# FPGA_Configuration.net
KiCad netlist of a schematic drawn in Altium Designer
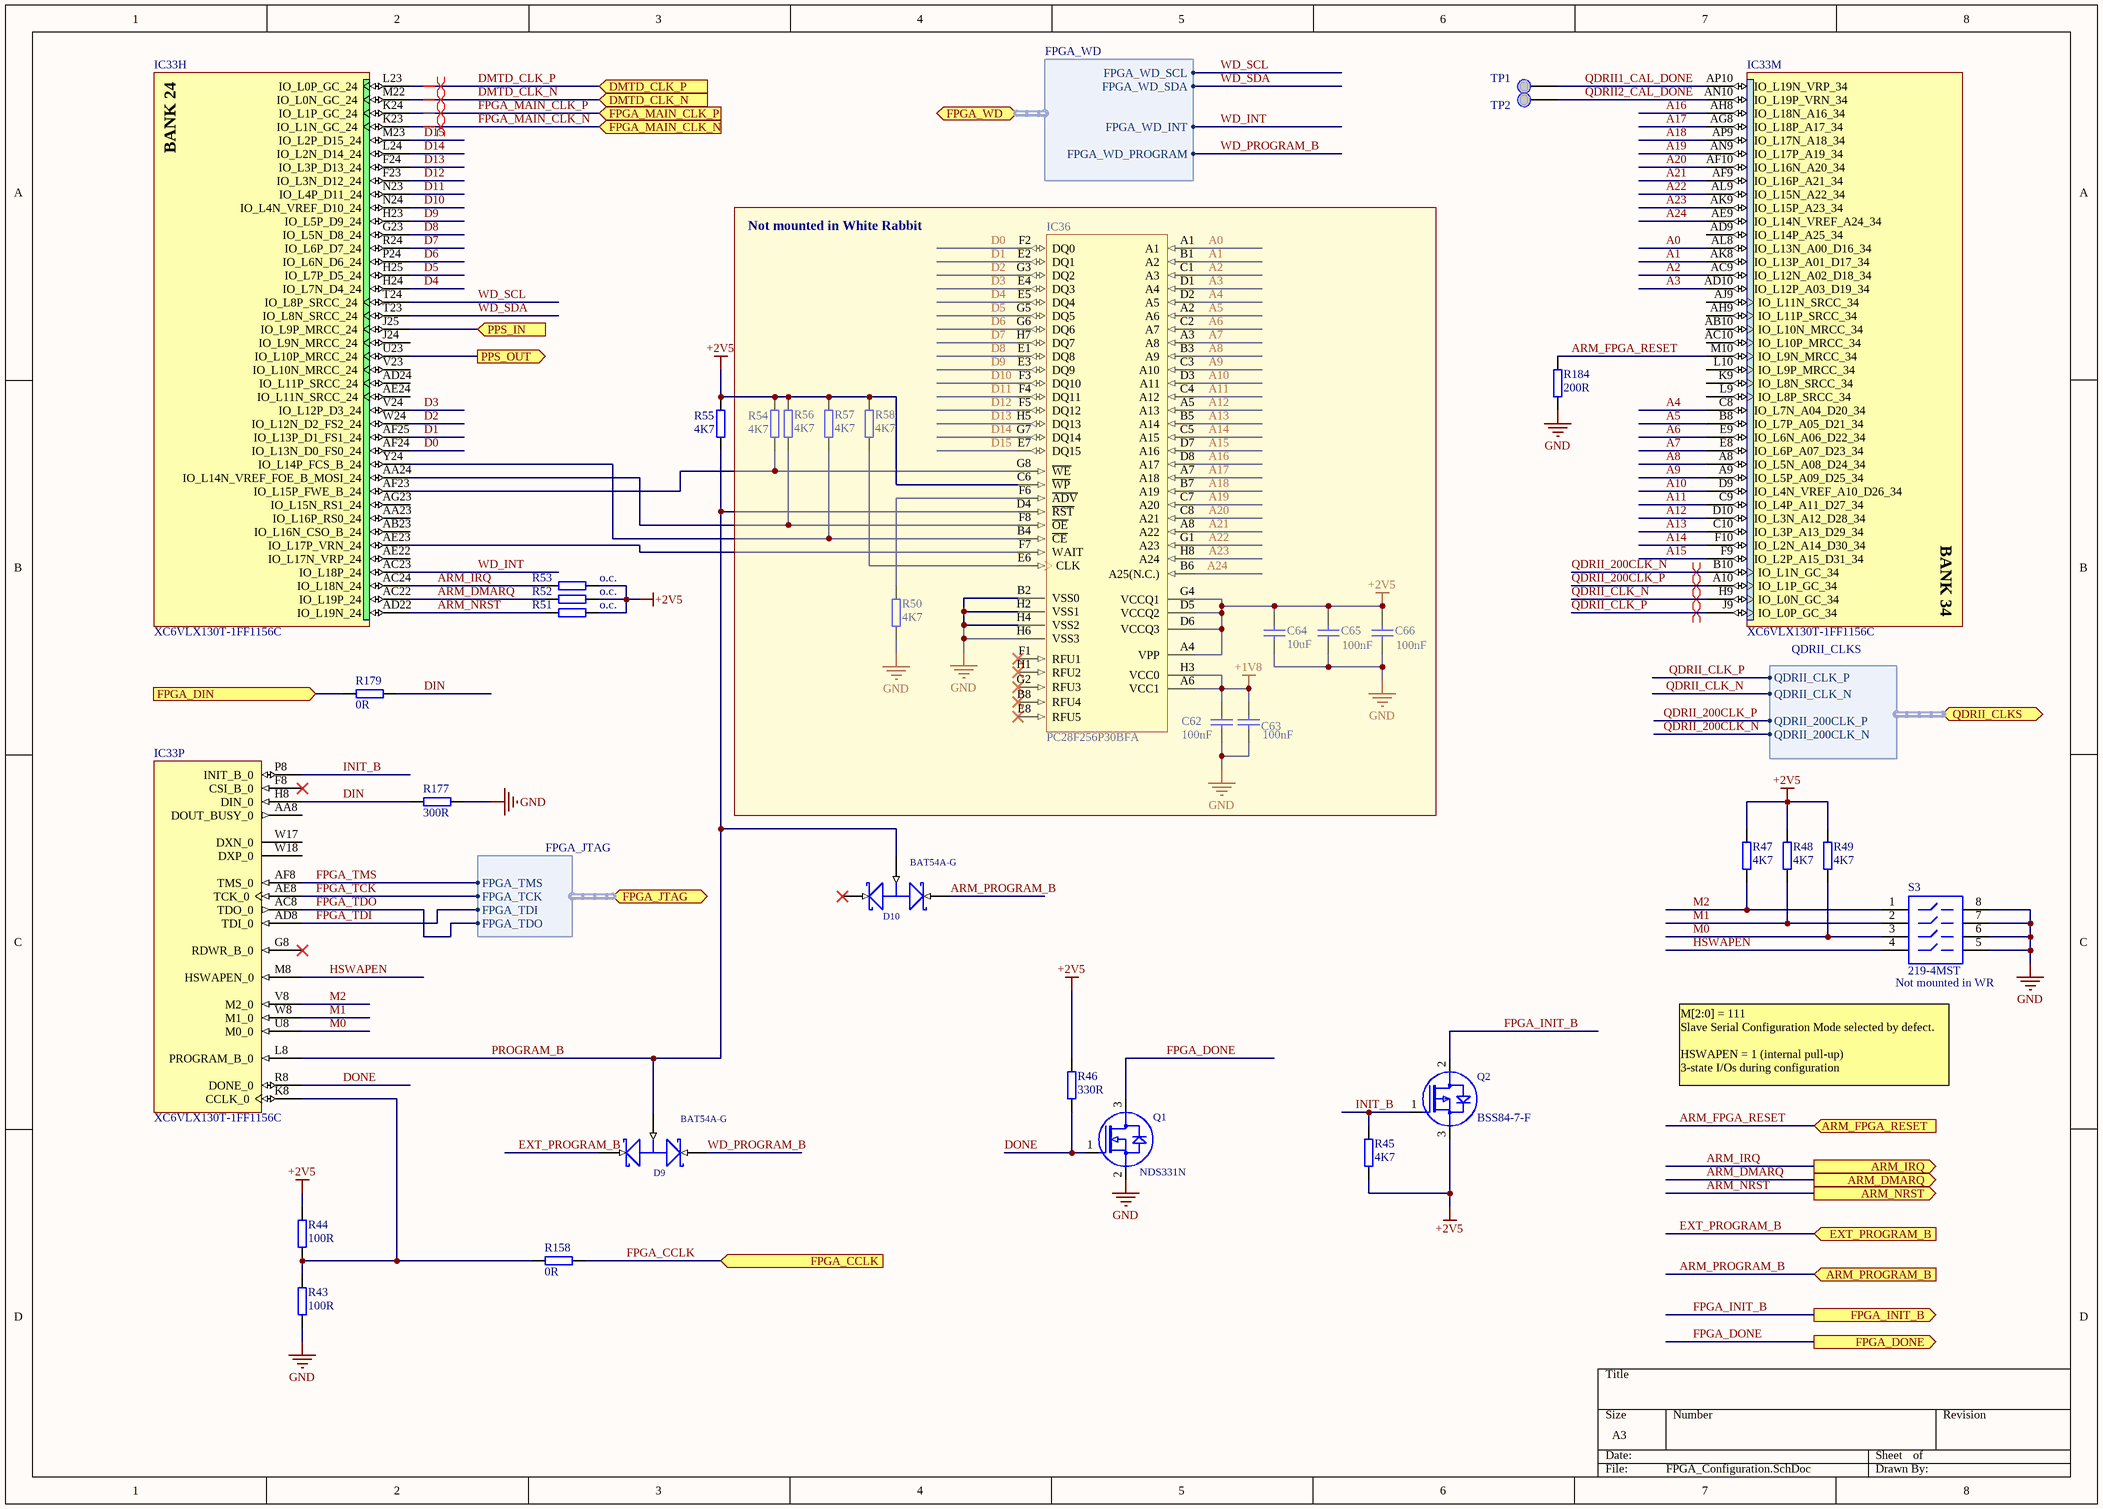
[diagram p0: FPGA_Configuration.SchDoc]

(export (version "E")
  (design (tool "Eeschema 10.0.6"))
  (components
    (comp (ref "C62")
      (value "100nF")
      (footprint "CC1005-0402")
      (description "Capacitor")
      (fields
        (field (name "TOLERANCE") "±10%")
        (field (name "VOLTAGE") "16V")
        (field (name "PUBLISHER") "Altium Limited")
      )
      (libsource (lib "wr_switch") (part "Cap"))
    )
    (comp (ref "C63")
      (value "100nF")
      (footprint "CC1005-0402")
      (description "Capacitor")
      (fields
        (field (name "TOLERANCE") "±10%")
        (field (name "VOLTAGE") "16V")
        (field (name "PUBLISHER") "Altium Limited")
      )
      (libsource (lib "wr_switch") (part "Cap"))
    )
    (comp (ref "C64")
      (value "10uF")
      (footprint "CC1608-0603")
      (description "Capacitor")
      (fields
        (field (name "TOLERANCE") "±20%")
        (field (name "VOLTAGE") "6.3V")
        (field (name "PUBLISHER") "Altium Limited")
      )
      (libsource (lib "wr_switch") (part "Cap"))
    )
    (comp (ref "C65")
      (value "100nF")
      (footprint "CC1005-0402")
      (description "Capacitor")
      (fields
        (field (name "TOLERANCE") "±10%")
        (field (name "VOLTAGE") "16V")
        (field (name "PUBLISHER") "Altium Limited")
      )
      (libsource (lib "wr_switch") (part "Cap"))
    )
    (comp (ref "C66")
      (value "100nF")
      (footprint "CC1005-0402")
      (description "Capacitor")
      (fields
        (field (name "TOLERANCE") "±10%")
        (field (name "VOLTAGE") "16V")
        (field (name "PUBLISHER") "Altium Limited")
      )
      (libsource (lib "wr_switch") (part "Cap"))
    )
    (comp (ref "D9")
      (value "BAT54A-G")
      (footprint "SOT23")
      (description "Schottky Barrier Double Diode")
      (fields (field (name "PUBLISHER") "Altium Limited"))
      (libsource (lib "wr_switch") (part "BAT54A.1"))
    )
    (comp (ref "D10")
      (value "BAT54A-G")
      (footprint "SOT23")
      (description "Schottky Barrier Double Diode")
      (fields (field (name "PUBLISHER") "Altium Limited"))
      (libsource (lib "wr_switch") (part "BAT54A.1"))
    )
    (comp (ref "IC33")
      (value "XC6VLX130T-1FF1156C")
      (footprint "FF1156")
      (fields (field (name "PUBLISHER") "Altium Limited"))
      (libsource (lib "Xilinx Virtex-6") (part "XC6VLX130T-1FF1156C"))
    )
    (comp (ref "IC36")
      (value "PC28F256P30BFA")
      (footprint "BGA64C100P8X8_1300X1000X120")
      (description "NOR Flash Memory, 256Mbit")
      (libsource (lib "wr_switch") (part "PC28F256P30BFA"))
    )
    (comp (ref "Q1")
      (value "NDS331N")
      (footprint "SOT23-3")
      (description "N-Channel Logic Level Enhancement Mode Field Effect Transistor")
      (libsource (lib "wr_switch") (part "NDS331N"))
    )
    (comp (ref "Q2")
      (value "FET-3PIN")
      (footprint "SOT-23")
      (description "P-Channel Logic Level Enhancement Mode Field Effect Transistor")
      (fields (field (name "MANF") "Diodes Inc.") (field (name "MANF_P/N") "BSS84-7-F"))
      (libsource (lib "wr_switch") (part "BSS84-7-F"))
    )
    (comp (ref "R43")
      (value "100R")
      (footprint "0402")
      (description "SMD Resistor")
      (fields (field (name "TOLERANCE") "±1%"))
      (libsource (lib "wr_switch") (part "RES_SMD"))
    )
    (comp (ref "R44")
      (value "100R")
      (footprint "0402")
      (description "SMD Resistor")
      (fields (field (name "TOLERANCE") "±1%"))
      (libsource (lib "wr_switch") (part "RES_SMD"))
    )
    (comp (ref "R45")
      (value "4K7")
      (footprint "0402")
      (description "SMD Resistor")
      (fields (field (name "TOLERANCE") "±1%"))
      (libsource (lib "wr_switch") (part "RES_SMD"))
    )
    (comp (ref "R46")
      (value "330R")
      (footprint "0402")
      (description "SMD Resistor")
      (fields (field (name "TOLERANCE") "±1%"))
      (libsource (lib "wr_switch") (part "RES_SMD"))
    )
    (comp (ref "R47")
      (value "4K7")
      (footprint "0402")
      (description "SMD Resistor")
      (fields (field (name "TOLERANCE") "±1%"))
      (libsource (lib "wr_switch") (part "RES_SMD"))
    )
    (comp (ref "R48")
      (value "4K7")
      (footprint "0402")
      (description "SMD Resistor")
      (fields (field (name "TOLERANCE") "±1%"))
      (libsource (lib "wr_switch") (part "RES_SMD"))
    )
    (comp (ref "R49")
      (value "4K7")
      (footprint "0402")
      (description "SMD Resistor")
      (fields (field (name "TOLERANCE") "±1%"))
      (libsource (lib "wr_switch") (part "RES_SMD"))
    )
    (comp (ref "R50")
      (value "4K7")
      (footprint "0402")
      (description "SMD Resistor")
      (fields (field (name "TOLERANCE") "±1%"))
      (libsource (lib "wr_switch") (part "RES_SMD"))
    )
    (comp (ref "R51")
      (value "o.c.")
      (footprint "0402")
      (description "SMD Resistor")
      (libsource (lib "wr_switch") (part "RES_SMD"))
    )
    (comp (ref "R52")
      (value "o.c.")
      (footprint "0402")
      (description "SMD Resistor")
      (libsource (lib "wr_switch") (part "RES_SMD"))
    )
    (comp (ref "R53")
      (value "o.c.")
      (footprint "0402")
      (description "SMD Resistor")
      (libsource (lib "wr_switch") (part "RES_SMD"))
    )
    (comp (ref "R54")
      (value "4K7")
      (footprint "0402")
      (description "SMD Resistor")
      (fields (field (name "TOLERANCE") "±1%"))
      (libsource (lib "wr_switch") (part "RES_SMD"))
    )
    (comp (ref "R55")
      (value "4K7")
      (footprint "0402")
      (description "SMD Resistor")
      (fields (field (name "TOLERANCE") "±1%"))
      (libsource (lib "wr_switch") (part "RES_SMD"))
    )
    (comp (ref "R56")
      (value "4K7")
      (footprint "0402")
      (description "SMD Resistor")
      (fields (field (name "TOLERANCE") "±1%"))
      (libsource (lib "wr_switch") (part "RES_SMD"))
    )
    (comp (ref "R57")
      (value "4K7")
      (footprint "0402")
      (description "SMD Resistor")
      (fields (field (name "TOLERANCE") "±1%"))
      (libsource (lib "wr_switch") (part "RES_SMD"))
    )
    (comp (ref "R58")
      (value "4K7")
      (footprint "0402")
      (description "SMD Resistor")
      (fields (field (name "TOLERANCE") "±1%"))
      (libsource (lib "wr_switch") (part "RES_SMD"))
    )
    (comp (ref "R158")
      (value "0R")
      (footprint "0402")
      (description "SMD Resistor")
      (fields (field (name "TOLERANCE") "Jumper"))
      (libsource (lib "wr_switch") (part "RES_SMD"))
    )
    (comp (ref "R177")
      (value "300R")
      (footprint "0402")
      (description "SMD Resistor")
      (fields (field (name "TOLERANCE") "±1%"))
      (libsource (lib "wr_switch") (part "RES_SMD"))
    )
    (comp (ref "R179")
      (value "0R")
      (footprint "0402")
      (description "SMD Resistor")
      (fields (field (name "TOLERANCE") "Jumper"))
      (libsource (lib "wr_switch") (part "RES_SMD"))
    )
    (comp (ref "R184")
      (value "200R")
      (footprint "0402")
      (description "SMD Resistor")
      (fields (field (name "TOLERANCE") "±1%"))
      (libsource (lib "wr_switch") (part "RES_SMD"))
    )
    (comp (ref "S3")
      (value "219-4MST")
      (footprint "7S_WR:NHDS-8")
      (description "4 Positions DIP SWITCH")
      (fields
        (field (name "MANUFACTURER") "CTS Electrocomponents")
        (field (name "MOUNTED") "Not mounted in WR")
      )
      (libsource (lib "wr_switch") (part "SW-DIP4"))
    )
    (comp (ref "TP1")
      (value "Test Point")
      (footprint "TEST_PAD_1mm")
      (description "SMD 1mm Test Point")
      (libsource (lib "wr_switch") (part "TEST_POINT"))
    )
    (comp (ref "TP2")
      (value "Test Point")
      (footprint "TEST_PAD_1mm")
      (description "SMD 1mm Test Point")
      (libsource (lib "wr_switch") (part "TEST_POINT"))
    )
  )
  (nets
    (net (code "4") (name "+1V8") (class "Default")
      (node (ref "C62") (pin "2") (pinfunction "2_2") (pintype "passive"))
      (node (ref "C63") (pin "2") (pinfunction "2_2") (pintype "passive"))
      (node (ref "IC36") (pin "A6") (pinfunction "VCC1_A6") (pintype "power_in"))
      (node (ref "IC36") (pin "H3") (pinfunction "VCC0_H3") (pintype "power_in"))
    )
    (net (code "5") (name "+2V5") (class "Default")
      (node (ref "C64") (pin "2") (pinfunction "2_2") (pintype "passive"))
      (node (ref "C65") (pin "2") (pinfunction "2_2") (pintype "passive"))
      (node (ref "C66") (pin "2") (pinfunction "2_2") (pintype "passive"))
      (node (ref "IC36") (pin "A4") (pinfunction "VPP_A4") (pintype "passive"))
      (node (ref "IC36") (pin "C6") (pinfunction "~{WP}_C6") (pintype "input"))
      (node (ref "IC36") (pin "D5") (pinfunction "VCCQ2_D5") (pintype "power_in"))
      (node (ref "IC36") (pin "D6") (pinfunction "VCCQ3_D6") (pintype "power_in"))
      (node (ref "IC36") (pin "G4") (pinfunction "VCCQ1_G4") (pintype "power_in"))
      (node (ref "Q2") (pin "3") (pinfunction "SOURCE_3") (pintype "passive"))
      (node (ref "R44") (pin "2") (pinfunction "2_2") (pintype "passive"))
      (node (ref "R45") (pin "1") (pinfunction "1_1") (pintype "passive"))
      (node (ref "R46") (pin "2") (pinfunction "2_2") (pintype "passive"))
      (node (ref "R47") (pin "2") (pinfunction "2_2") (pintype "passive"))
      (node (ref "R48") (pin "2") (pinfunction "2_2") (pintype "passive"))
      (node (ref "R49") (pin "2") (pinfunction "2_2") (pintype "passive"))
      (node (ref "R51") (pin "1") (pinfunction "1_1") (pintype "passive"))
      (node (ref "R52") (pin "1") (pinfunction "1_1") (pintype "passive"))
      (node (ref "R53") (pin "1") (pinfunction "1_1") (pintype "passive"))
      (node (ref "R54") (pin "2") (pinfunction "2_2") (pintype "passive"))
      (node (ref "R55") (pin "2") (pinfunction "2_2") (pintype "passive"))
      (node (ref "R56") (pin "2") (pinfunction "2_2") (pintype "passive"))
      (node (ref "R57") (pin "2") (pinfunction "2_2") (pintype "passive"))
      (node (ref "R58") (pin "2") (pinfunction "2_2") (pintype "passive"))
    )
    (net (code "6") (name "/A0") (class "Default")
      (node (ref "IC33") (pin "AL8") (pinfunction "IO_L13N_A00_D16_34_AL8") (pintype "bidirectional"))
      (node (ref "IC36") (pin "A1") (pinfunction "A1_A1") (pintype "input"))
    )
    (net (code "7") (name "/A1") (class "Default")
      (node (ref "IC33") (pin "AK8") (pinfunction "IO_L13P_A01_D17_34_AK8") (pintype "bidirectional"))
      (node (ref "IC36") (pin "B1") (pinfunction "A2_B1") (pintype "input"))
    )
    (net (code "8") (name "/A2") (class "Default")
      (node (ref "IC33") (pin "AC9") (pinfunction "IO_L12N_A02_D18_34_AC9") (pintype "bidirectional"))
      (node (ref "IC36") (pin "C1") (pinfunction "A3_C1") (pintype "input"))
    )
    (net (code "9") (name "/A3") (class "Default")
      (node (ref "IC33") (pin "AD10") (pinfunction "IO_L12P_A03_D19_34_AD10") (pintype "bidirectional"))
      (node (ref "IC36") (pin "D1") (pinfunction "A4_D1") (pintype "input"))
    )
    (net (code "10") (name "/A4") (class "Default")
      (node (ref "IC33") (pin "C8") (pinfunction "IO_L7N_A04_D20_34_C8") (pintype "bidirectional"))
      (node (ref "IC36") (pin "D2") (pinfunction "A5_D2") (pintype "input"))
    )
    (net (code "11") (name "/A5") (class "Default")
      (node (ref "IC33") (pin "B8") (pinfunction "IO_L7P_A05_D21_34_B8") (pintype "bidirectional"))
      (node (ref "IC36") (pin "A2") (pinfunction "A6_A2") (pintype "input"))
    )
    (net (code "12") (name "/A6") (class "Default")
      (node (ref "IC33") (pin "E9") (pinfunction "IO_L6N_A06_D22_34_E9") (pintype "bidirectional"))
      (node (ref "IC36") (pin "C2") (pinfunction "A7_C2") (pintype "input"))
    )
    (net (code "13") (name "/A7") (class "Default")
      (node (ref "IC33") (pin "E8") (pinfunction "IO_L6P_A07_D23_34_E8") (pintype "bidirectional"))
      (node (ref "IC36") (pin "A3") (pinfunction "A8_A3") (pintype "input"))
    )
    (net (code "14") (name "/A8") (class "Default")
      (node (ref "IC33") (pin "A8") (pinfunction "IO_L5N_A08_D24_34_A8") (pintype "bidirectional"))
      (node (ref "IC36") (pin "B3") (pinfunction "A9_B3") (pintype "input"))
    )
    (net (code "15") (name "/A9") (class "Default")
      (node (ref "IC33") (pin "A9") (pinfunction "IO_L5P_A09_D25_34_A9") (pintype "bidirectional"))
      (node (ref "IC36") (pin "C3") (pinfunction "A10_C3") (pintype "input"))
    )
    (net (code "16") (name "/A10") (class "Default")
      (node (ref "IC33") (pin "D9") (pinfunction "IO_L4N_VREF_A10_D26_34_D9") (pintype "bidirectional"))
      (node (ref "IC36") (pin "D3") (pinfunction "A11_D3") (pintype "input"))
    )
    (net (code "17") (name "/A11") (class "Default")
      (node (ref "IC33") (pin "C9") (pinfunction "IO_L4P_A11_D27_34_C9") (pintype "bidirectional"))
      (node (ref "IC36") (pin "C4") (pinfunction "A12_C4") (pintype "input"))
    )
    (net (code "18") (name "/A12") (class "Default")
      (node (ref "IC33") (pin "D10") (pinfunction "IO_L3N_A12_D28_34_D10") (pintype "bidirectional"))
      (node (ref "IC36") (pin "A5") (pinfunction "A13_A5") (pintype "input"))
    )
    (net (code "19") (name "/A13") (class "Default")
      (node (ref "IC33") (pin "C10") (pinfunction "IO_L3P_A13_D29_34_C10") (pintype "bidirectional"))
      (node (ref "IC36") (pin "B5") (pinfunction "A14_B5") (pintype "input"))
    )
    (net (code "20") (name "/A14") (class "Default")
      (node (ref "IC33") (pin "F10") (pinfunction "IO_L2N_A14_D30_34_F10") (pintype "bidirectional"))
      (node (ref "IC36") (pin "C5") (pinfunction "A15_C5") (pintype "input"))
    )
    (net (code "21") (name "/A15") (class "Default")
      (node (ref "IC33") (pin "F9") (pinfunction "IO_L2P_A15_D31_34_F9") (pintype "bidirectional"))
      (node (ref "IC36") (pin "D7") (pinfunction "A16_D7") (pintype "input"))
    )
    (net (code "22") (name "/A16") (class "Default")
      (node (ref "IC33") (pin "AH8") (pinfunction "IO_L18N_A16_34_AH8") (pintype "bidirectional"))
      (node (ref "IC36") (pin "D8") (pinfunction "A17_D8") (pintype "input"))
    )
    (net (code "23") (name "/A17") (class "Default")
      (node (ref "IC33") (pin "AG8") (pinfunction "IO_L18P_A17_34_AG8") (pintype "bidirectional"))
      (node (ref "IC36") (pin "A7") (pinfunction "A18_A7") (pintype "input"))
    )
    (net (code "24") (name "/A18") (class "Default")
      (node (ref "IC33") (pin "AP9") (pinfunction "IO_L17N_A18_34_AP9") (pintype "bidirectional"))
      (node (ref "IC36") (pin "B7") (pinfunction "A19_B7") (pintype "input"))
    )
    (net (code "25") (name "/A19") (class "Default")
      (node (ref "IC33") (pin "AN9") (pinfunction "IO_L17P_A19_34_AN9") (pintype "bidirectional"))
      (node (ref "IC36") (pin "C7") (pinfunction "A20_C7") (pintype "input"))
    )
    (net (code "26") (name "/A20") (class "Default")
      (node (ref "IC33") (pin "AF10") (pinfunction "IO_L16N_A20_34_AF10") (pintype "bidirectional"))
      (node (ref "IC36") (pin "C8") (pinfunction "A21_C8") (pintype "input"))
    )
    (net (code "27") (name "/A21") (class "Default")
      (node (ref "IC33") (pin "AF9") (pinfunction "IO_L16P_A21_34_AF9") (pintype "bidirectional"))
      (node (ref "IC36") (pin "A8") (pinfunction "A22_A8") (pintype "input"))
    )
    (net (code "28") (name "/A22") (class "Default")
      (node (ref "IC33") (pin "AL9") (pinfunction "IO_L15N_A22_34_AL9") (pintype "bidirectional"))
      (node (ref "IC36") (pin "G1") (pinfunction "A23_G1") (pintype "input"))
    )
    (net (code "29") (name "/A23") (class "Default")
      (node (ref "IC33") (pin "AK9") (pinfunction "IO_L15P_A23_34_AK9") (pintype "bidirectional"))
      (node (ref "IC36") (pin "H8") (pinfunction "A24_H8") (pintype "input"))
    )
    (net (code "30") (name "/A24") (class "Default")
      (node (ref "IC33") (pin "AE9") (pinfunction "IO_L14N_VREF_A24_34_AE9") (pintype "bidirectional"))
      (node (ref "IC36") (pin "B6") (pinfunction "A25(N.C.)_B6") (pintype "input"))
    )
    (net (code "31") (name "/ARM_DMARQ") (class "Default")
      (node (ref "IC33") (pin "AC22") (pinfunction "IO_L19P_24_AC22") (pintype "bidirectional"))
      (node (ref "R52") (pin "2") (pinfunction "2_2") (pintype "passive"))
    )
    (net (code "32") (name "/ARM_FPGA_RESET") (class "Default")
      (node (ref "IC33") (pin "M10") (pinfunction "IO_L9N_MRCC_34_M10") (pintype "bidirectional"))
      (node (ref "R184") (pin "2") (pinfunction "2_2") (pintype "passive"))
    )
    (net (code "33") (name "/ARM_IRQ") (class "Default")
      (node (ref "IC33") (pin "AC24") (pinfunction "IO_L18N_24_AC24") (pintype "bidirectional"))
      (node (ref "R53") (pin "2") (pinfunction "2_2") (pintype "passive"))
    )
    (net (code "34") (name "/ARM_NRST") (class "Default")
      (node (ref "IC33") (pin "AD22") (pinfunction "IO_L19N_24_AD22") (pintype "bidirectional"))
      (node (ref "R51") (pin "2") (pinfunction "2_2") (pintype "passive"))
    )
    (net (code "35") (name "/ARM_PROGRAM_B") (class "Default")
      (node (ref "D10") (pin "2") (pinfunction "K2_2") (pintype "input"))
    )
    (net (code "36") (name "/D0") (class "Default")
      (node (ref "IC33") (pin "AF24") (pinfunction "IO_L13N_D0_FS0_24_AF24") (pintype "bidirectional"))
      (node (ref "IC36") (pin "F2") (pinfunction "DQ0_F2") (pintype "bidirectional"))
    )
    (net (code "37") (name "/D1") (class "Default")
      (node (ref "IC33") (pin "AF25") (pinfunction "IO_L13P_D1_FS1_24_AF25") (pintype "bidirectional"))
      (node (ref "IC36") (pin "E2") (pinfunction "DQ1_E2") (pintype "bidirectional"))
    )
    (net (code "38") (name "/D2") (class "Default")
      (node (ref "IC33") (pin "W24") (pinfunction "IO_L12N_D2_FS2_24_W24") (pintype "bidirectional"))
      (node (ref "IC36") (pin "G3") (pinfunction "DQ2_G3") (pintype "bidirectional"))
    )
    (net (code "39") (name "/D3") (class "Default")
      (node (ref "IC33") (pin "V24") (pinfunction "IO_L12P_D3_24_V24") (pintype "bidirectional"))
      (node (ref "IC36") (pin "E4") (pinfunction "DQ3_E4") (pintype "bidirectional"))
    )
    (net (code "40") (name "/D4") (class "Default")
      (node (ref "IC33") (pin "H24") (pinfunction "IO_L7N_D4_24_H24") (pintype "bidirectional"))
      (node (ref "IC36") (pin "E5") (pinfunction "DQ4_E5") (pintype "bidirectional"))
    )
    (net (code "41") (name "/D5") (class "Default")
      (node (ref "IC33") (pin "H25") (pinfunction "IO_L7P_D5_24_H25") (pintype "bidirectional"))
      (node (ref "IC36") (pin "G5") (pinfunction "DQ5_G5") (pintype "bidirectional"))
    )
    (net (code "42") (name "/D6") (class "Default")
      (node (ref "IC33") (pin "P24") (pinfunction "IO_L6N_D6_24_P24") (pintype "bidirectional"))
      (node (ref "IC36") (pin "G6") (pinfunction "DQ6_G6") (pintype "bidirectional"))
    )
    (net (code "43") (name "/D7") (class "Default")
      (node (ref "IC33") (pin "R24") (pinfunction "IO_L6P_D7_24_R24") (pintype "bidirectional"))
      (node (ref "IC36") (pin "H7") (pinfunction "DQ7_H7") (pintype "bidirectional"))
    )
    (net (code "44") (name "/D8") (class "Default")
      (node (ref "IC33") (pin "G23") (pinfunction "IO_L5N_D8_24_G23") (pintype "bidirectional"))
      (node (ref "IC36") (pin "E1") (pinfunction "DQ8_E1") (pintype "bidirectional"))
    )
    (net (code "45") (name "/D9") (class "Default")
      (node (ref "IC33") (pin "H23") (pinfunction "IO_L5P_D9_24_H23") (pintype "bidirectional"))
      (node (ref "IC36") (pin "E3") (pinfunction "DQ9_E3") (pintype "bidirectional"))
    )
    (net (code "46") (name "/D10") (class "Default")
      (node (ref "IC33") (pin "N24") (pinfunction "IO_L4N_VREF_D10_24_N24") (pintype "bidirectional"))
      (node (ref "IC36") (pin "F3") (pinfunction "DQ10_F3") (pintype "bidirectional"))
    )
    (net (code "47") (name "/D11") (class "Default")
      (node (ref "IC33") (pin "N23") (pinfunction "IO_L4P_D11_24_N23") (pintype "bidirectional"))
      (node (ref "IC36") (pin "F4") (pinfunction "DQ11_F4") (pintype "bidirectional"))
    )
    (net (code "48") (name "/D12") (class "Default")
      (node (ref "IC33") (pin "F23") (pinfunction "IO_L3N_D12_24_F23") (pintype "bidirectional"))
      (node (ref "IC36") (pin "F5") (pinfunction "DQ12_F5") (pintype "bidirectional"))
    )
    (net (code "49") (name "/D13") (class "Default")
      (node (ref "IC33") (pin "F24") (pinfunction "IO_L3P_D13_24_F24") (pintype "bidirectional"))
      (node (ref "IC36") (pin "H5") (pinfunction "DQ13_H5") (pintype "bidirectional"))
    )
    (net (code "50") (name "/D14") (class "Default")
      (node (ref "IC33") (pin "L24") (pinfunction "IO_L2N_D14_24_L24") (pintype "bidirectional"))
      (node (ref "IC36") (pin "G7") (pinfunction "DQ14_G7") (pintype "bidirectional"))
    )
    (net (code "51") (name "/D15") (class "Default")
      (node (ref "IC33") (pin "M23") (pinfunction "IO_L2P_D15_24_M23") (pintype "bidirectional"))
      (node (ref "IC36") (pin "E7") (pinfunction "DQ15_E7") (pintype "bidirectional"))
    )
    (net (code "52") (name "/DIN") (class "Default")
      (node (ref "IC33") (pin "H8") (pinfunction "DIN_0_H8") (pintype "input"))
      (node (ref "R177") (pin "2") (pinfunction "2_2") (pintype "passive"))
      (node (ref "R179") (pin "1") (pinfunction "1_1") (pintype "passive"))
    )
    (net (code "53") (name "/DMTD_CLK_N") (class "Default")
      (node (ref "IC33") (pin "M22") (pinfunction "IO_L0N_GC_24_M22") (pintype "bidirectional"))
    )
    (net (code "54") (name "/DMTD_CLK_P") (class "Default")
      (node (ref "IC33") (pin "L23") (pinfunction "IO_L0P_GC_24_L23") (pintype "bidirectional"))
    )
    (net (code "55") (name "/DONE") (class "Default")
      (node (ref "IC33") (pin "R8") (pinfunction "DONE_0_R8") (pintype "bidirectional"))
      (node (ref "Q1") (pin "1") (pinfunction "GATE_1") (pintype "passive"))
      (node (ref "R46") (pin "1") (pinfunction "1_1") (pintype "passive"))
    )
    (net (code "56") (name "/EXT_PROGRAM_B") (class "Default")
      (node (ref "D9") (pin "1") (pinfunction "K1_1") (pintype "input"))
    )
    (net (code "57") (name "/FPGA_CCLK") (class "Default")
      (node (ref "R158") (pin "1") (pinfunction "1_1") (pintype "passive"))
    )
    (net (code "58") (name "/FPGA_DIN") (class "Default")
      (node (ref "R179") (pin "2") (pinfunction "2_2") (pintype "passive"))
    )
    (net (code "59") (name "/FPGA_DONE") (class "Default")
      (node (ref "Q1") (pin "3") (pinfunction "DRAIN_3") (pintype "passive"))
    )
    (net (code "60") (name "/FPGA_INIT_B") (class "Default")
      (node (ref "Q2") (pin "2") (pinfunction "DRAIN_2") (pintype "passive"))
    )
    (net (code "61") (name "/FPGA_MAIN_CLK_N") (class "Default")
      (node (ref "IC33") (pin "K23") (pinfunction "IO_L1N_GC_24_K23") (pintype "bidirectional"))
    )
    (net (code "62") (name "/FPGA_MAIN_CLK_P") (class "Default")
      (node (ref "IC33") (pin "K24") (pinfunction "IO_L1P_GC_24_K24") (pintype "bidirectional"))
    )
    (net (code "63") (name "/FPGA_TCK") (class "Default")
      (node (ref "IC33") (pin "AE8") (pinfunction "TCK_0_AE8") (pintype "input"))
    )
    (net (code "64") (name "/FPGA_TDI") (class "Default")
      (node (ref "IC33") (pin "AD8") (pinfunction "TDI_0_AD8") (pintype "input"))
    )
    (net (code "65") (name "/FPGA_TDO") (class "Default")
      (node (ref "IC33") (pin "AC8") (pinfunction "TDO_0_AC8") (pintype "output"))
    )
    (net (code "66") (name "/FPGA_TMS") (class "Default")
      (node (ref "IC33") (pin "AF8") (pinfunction "TMS_0_AF8") (pintype "input"))
    )
    (net (code "67") (name "/HSWAPEN") (class "Default")
      (node (ref "IC33") (pin "M8") (pinfunction "HSWAPEN_0_M8") (pintype "input"))
      (node (ref "S3") (pin "4") (pinfunction "4_4") (pintype "passive"))
    )
    (net (code "68") (name "/INIT_B") (class "Default")
      (node (ref "IC33") (pin "P8") (pinfunction "INIT_B_0_P8") (pintype "bidirectional"))
      (node (ref "Q2") (pin "1") (pinfunction "GATE_1") (pintype "passive"))
      (node (ref "R45") (pin "2") (pinfunction "2_2") (pintype "passive"))
    )
    (net (code "69") (name "/M0") (class "Default")
      (node (ref "IC33") (pin "U8") (pinfunction "M0_0_U8") (pintype "input"))
      (node (ref "R49") (pin "1") (pinfunction "1_1") (pintype "passive"))
      (node (ref "S3") (pin "3") (pinfunction "3_3") (pintype "passive"))
    )
    (net (code "70") (name "/M1") (class "Default")
      (node (ref "IC33") (pin "W8") (pinfunction "M1_0_W8") (pintype "input"))
      (node (ref "R48") (pin "1") (pinfunction "1_1") (pintype "passive"))
      (node (ref "S3") (pin "2") (pinfunction "2_2") (pintype "passive"))
    )
    (net (code "71") (name "/M2") (class "Default")
      (node (ref "IC33") (pin "V8") (pinfunction "M2_0_V8") (pintype "input"))
      (node (ref "R47") (pin "1") (pinfunction "1_1") (pintype "passive"))
      (node (ref "S3") (pin "1") (pinfunction "1_1") (pintype "passive"))
    )
    (net (code "72") (name "/PPS_IN") (class "Default")
      (node (ref "IC33") (pin "J25") (pinfunction "IO_L9P_MRCC_24_J25") (pintype "bidirectional"))
    )
    (net (code "73") (name "/PPS_OUT") (class "Default")
      (node (ref "IC33") (pin "U23") (pinfunction "IO_L10P_MRCC_24_U23") (pintype "bidirectional"))
    )
    (net (code "74") (name "/PROGRAM_B") (class "Default")
      (node (ref "D10") (pin "3") (pinfunction "A_3") (pintype "input"))
      (node (ref "D9") (pin "3") (pinfunction "A_3") (pintype "input"))
      (node (ref "IC33") (pin "L8") (pinfunction "PROGRAM_B_0_L8") (pintype "input"))
      (node (ref "IC36") (pin "D4") (pinfunction "~{RST}_D4") (pintype "input"))
      (node (ref "R55") (pin "1") (pinfunction "1_1") (pintype "passive"))
    )
    (net (code "75") (name "/QDRII1_CAL_DONE") (class "Default")
      (node (ref "IC33") (pin "AP10") (pinfunction "IO_L19N_VRP_34_AP10") (pintype "bidirectional"))
      (node (ref "TP1") (pin "1") (pinfunction "TP_1") (pintype "passive"))
    )
    (net (code "76") (name "/QDRII2_CAL_DONE") (class "Default")
      (node (ref "IC33") (pin "AN10") (pinfunction "IO_L19P_VRN_34_AN10") (pintype "bidirectional"))
      (node (ref "TP2") (pin "1") (pinfunction "TP_1") (pintype "passive"))
    )
    (net (code "77") (name "/QDRII_200CLK_N") (class "Default")
      (node (ref "IC33") (pin "B10") (pinfunction "IO_L1N_GC_34_B10") (pintype "bidirectional"))
    )
    (net (code "78") (name "/QDRII_200CLK_P") (class "Default")
      (node (ref "IC33") (pin "A10") (pinfunction "IO_L1P_GC_34_A10") (pintype "bidirectional"))
    )
    (net (code "79") (name "/QDRII_CLK_N") (class "Default")
      (node (ref "IC33") (pin "H9") (pinfunction "IO_L0N_GC_34_H9") (pintype "bidirectional"))
    )
    (net (code "80") (name "/QDRII_CLK_P") (class "Default")
      (node (ref "IC33") (pin "J9") (pinfunction "IO_L0P_GC_34_J9") (pintype "bidirectional"))
    )
    (net (code "81") (name "/WD_INT") (class "Default")
      (node (ref "IC33") (pin "AC23") (pinfunction "IO_L18P_24_AC23") (pintype "bidirectional"))
    )
    (net (code "82") (name "/WD_PROGRAM_B") (class "Default")
      (node (ref "D9") (pin "2") (pinfunction "K2_2") (pintype "input"))
    )
    (net (code "83") (name "/WD_SCL") (class "Default")
      (node (ref "IC33") (pin "T24") (pinfunction "IO_L8P_SRCC_24_T24") (pintype "bidirectional"))
    )
    (net (code "84") (name "/WD_SDA") (class "Default")
      (node (ref "IC33") (pin "T23") (pinfunction "IO_L8N_SRCC_24_T23") (pintype "bidirectional"))
    )
    (net (code "88") (name "GND") (class "Default")
      (node (ref "C62") (pin "1") (pinfunction "1_1") (pintype "passive"))
      (node (ref "C63") (pin "1") (pinfunction "1_1") (pintype "passive"))
      (node (ref "C64") (pin "1") (pinfunction "1_1") (pintype "passive"))
      (node (ref "C65") (pin "1") (pinfunction "1_1") (pintype "passive"))
      (node (ref "C66") (pin "1") (pinfunction "1_1") (pintype "passive"))
      (node (ref "IC36") (pin "B2") (pinfunction "VSS0_B2") (pintype "power_in"))
      (node (ref "IC36") (pin "H2") (pinfunction "VSS1_H2") (pintype "power_in"))
      (node (ref "IC36") (pin "H4") (pinfunction "VSS2_H4") (pintype "power_in"))
      (node (ref "IC36") (pin "H6") (pinfunction "VSS3_H6") (pintype "power_in"))
      (node (ref "Q1") (pin "2") (pinfunction "SOURCE_2") (pintype "passive"))
      (node (ref "R177") (pin "1") (pinfunction "1_1") (pintype "passive"))
      (node (ref "R184") (pin "1") (pinfunction "1_1") (pintype "passive"))
      (node (ref "R43") (pin "1") (pinfunction "1_1") (pintype "passive"))
      (node (ref "R50") (pin "1") (pinfunction "1_1") (pintype "passive"))
      (node (ref "S3") (pin "5") (pinfunction "5_5") (pintype "passive"))
      (node (ref "S3") (pin "6") (pinfunction "6_6") (pintype "passive"))
      (node (ref "S3") (pin "7") (pinfunction "7_7") (pintype "passive"))
      (node (ref "S3") (pin "8") (pinfunction "8_8") (pintype "passive"))
    )
    (net (code "89") (name "Net-(IC33H-IO_L14N_VREF_FOE_B_MOSI_24)") (class "Default")
      (node (ref "IC33") (pin "AA24") (pinfunction "IO_L14N_VREF_FOE_B_MOSI_24_AA24") (pintype "bidirectional"))
      (node (ref "IC36") (pin "F8") (pinfunction "~{OE}_F8") (pintype "input"))
      (node (ref "R56") (pin "1") (pinfunction "1_1") (pintype "passive"))
    )
    (net (code "90") (name "Net-(IC33H-IO_L14P_FCS_B_24)") (class "Default")
      (node (ref "IC33") (pin "Y24") (pinfunction "IO_L14P_FCS_B_24_Y24") (pintype "bidirectional"))
      (node (ref "IC36") (pin "B4") (pinfunction "~{CE}_B4") (pintype "input"))
      (node (ref "R57") (pin "1") (pinfunction "1_1") (pintype "passive"))
    )
    (net (code "91") (name "Net-(IC33H-IO_L15P_FWE_B_24)") (class "Default")
      (node (ref "IC33") (pin "AF23") (pinfunction "IO_L15P_FWE_B_24_AF23") (pintype "bidirectional"))
      (node (ref "IC36") (pin "G8") (pinfunction "~{WE}_G8") (pintype "input"))
      (node (ref "R54") (pin "1") (pinfunction "1_1") (pintype "passive"))
    )
    (net (code "92") (name "Net-(IC33H-IO_L17P_VRN_24)") (class "Default")
      (node (ref "IC33") (pin "AE23") (pinfunction "IO_L17P_VRN_24_AE23") (pintype "bidirectional"))
      (node (ref "IC36") (pin "F7") (pinfunction "WAIT_F7") (pintype "input"))
    )
    (net (code "93") (name "Net-(IC33P-CCLK_0)") (class "Default")
      (node (ref "IC33") (pin "K8") (pinfunction "CCLK_0_K8") (pintype "bidirectional"))
      (node (ref "R158") (pin "2") (pinfunction "2_2") (pintype "passive"))
      (node (ref "R43") (pin "2") (pinfunction "2_2") (pintype "passive"))
      (node (ref "R44") (pin "1") (pinfunction "1_1") (pintype "passive"))
    )
    (net (code "94") (name "Net-(IC36-CLK)") (class "Default")
      (node (ref "IC36") (pin "E6") (pinfunction "CLK_E6") (pintype "input"))
      (node (ref "R58") (pin "1") (pinfunction "1_1") (pintype "passive"))
    )
    (net (code "95") (name "Net-(IC36-~{ADV})") (class "Default")
      (node (ref "IC36") (pin "F6") (pinfunction "~{ADV}_F6") (pintype "input"))
      (node (ref "R50") (pin "2") (pinfunction "2_2") (pintype "passive"))
    )
    (net (code "96") (name "unconnected-(D10-K1-Pad1)") (class "Default")
      (node (ref "D10") (pin "1") (pinfunction "K1_1") (pintype "input+no_connect"))
    )
    (net (code "97") (name "unconnected-(IC33H-IO_L9N_MRCC_24-PadJ24)") (class "Default")
      (node (ref "IC33") (pin "J24") (pinfunction "IO_L9N_MRCC_24_J24") (pintype "bidirectional"))
    )
    (net (code "98") (name "unconnected-(IC33H-IO_L10N_MRCC_24-PadV23)") (class "Default")
      (node (ref "IC33") (pin "V23") (pinfunction "IO_L10N_MRCC_24_V23") (pintype "bidirectional"))
    )
    (net (code "99") (name "unconnected-(IC33H-IO_L11N_SRCC_24-PadAE24)") (class "Default")
      (node (ref "IC33") (pin "AE24") (pinfunction "IO_L11N_SRCC_24_AE24") (pintype "bidirectional"))
    )
    (net (code "100") (name "unconnected-(IC33H-IO_L11P_SRCC_24-PadAD24)") (class "Default")
      (node (ref "IC33") (pin "AD24") (pinfunction "IO_L11P_SRCC_24_AD24") (pintype "bidirectional"))
    )
    (net (code "101") (name "unconnected-(IC33H-IO_L15N_RS1_24-PadAG23)") (class "Default")
      (node (ref "IC33") (pin "AG23") (pinfunction "IO_L15N_RS1_24_AG23") (pintype "bidirectional"))
    )
    (net (code "102") (name "unconnected-(IC33H-IO_L16N_CSO_B_24-PadAB23)") (class "Default")
      (node (ref "IC33") (pin "AB23") (pinfunction "IO_L16N_CSO_B_24_AB23") (pintype "bidirectional"))
    )
    (net (code "103") (name "unconnected-(IC33H-IO_L16P_RS0_24-PadAA23)") (class "Default")
      (node (ref "IC33") (pin "AA23") (pinfunction "IO_L16P_RS0_24_AA23") (pintype "bidirectional"))
    )
    (net (code "104") (name "unconnected-(IC33H-IO_L17N_VRP_24-PadAE22)") (class "Default")
      (node (ref "IC33") (pin "AE22") (pinfunction "IO_L17N_VRP_24_AE22") (pintype "bidirectional"))
    )
    (net (code "105") (name "unconnected-(IC33M-IO_L8N_SRCC_34-PadK9)") (class "Default")
      (node (ref "IC33") (pin "K9") (pinfunction "IO_L8N_SRCC_34_K9") (pintype "bidirectional"))
    )
    (net (code "106") (name "unconnected-(IC33M-IO_L8P_SRCC_34-PadL9)") (class "Default")
      (node (ref "IC33") (pin "L9") (pinfunction "IO_L8P_SRCC_34_L9") (pintype "bidirectional"))
    )
    (net (code "107") (name "unconnected-(IC33M-IO_L9P_MRCC_34-PadL10)") (class "Default")
      (node (ref "IC33") (pin "L10") (pinfunction "IO_L9P_MRCC_34_L10") (pintype "bidirectional"))
    )
    (net (code "108") (name "unconnected-(IC33M-IO_L10N_MRCC_34-PadAB10)") (class "Default")
      (node (ref "IC33") (pin "AB10") (pinfunction "IO_L10N_MRCC_34_AB10") (pintype "bidirectional"))
    )
    (net (code "109") (name "unconnected-(IC33M-IO_L10P_MRCC_34-PadAC10)") (class "Default")
      (node (ref "IC33") (pin "AC10") (pinfunction "IO_L10P_MRCC_34_AC10") (pintype "bidirectional"))
    )
    (net (code "110") (name "unconnected-(IC33M-IO_L11N_SRCC_34-PadAJ9)") (class "Default")
      (node (ref "IC33") (pin "AJ9") (pinfunction "IO_L11N_SRCC_34_AJ9") (pintype "bidirectional"))
    )
    (net (code "111") (name "unconnected-(IC33M-IO_L11P_SRCC_34-PadAH9)") (class "Default")
      (node (ref "IC33") (pin "AH9") (pinfunction "IO_L11P_SRCC_34_AH9") (pintype "bidirectional"))
    )
    (net (code "112") (name "unconnected-(IC33M-IO_L14P_A25_34-PadAD9)") (class "Default")
      (node (ref "IC33") (pin "AD9") (pinfunction "IO_L14P_A25_34_AD9") (pintype "bidirectional"))
    )
    (net (code "113") (name "unconnected-(IC33P-CSI_B_0-PadF8)") (class "Default")
      (node (ref "IC33") (pin "F8") (pinfunction "CSI_B_0_F8") (pintype "input+no_connect"))
    )
    (net (code "114") (name "unconnected-(IC33P-DOUT_BUSY_0-PadAA8)") (class "Default")
      (node (ref "IC33") (pin "AA8") (pinfunction "DOUT_BUSY_0_AA8") (pintype "output"))
    )
    (net (code "115") (name "unconnected-(IC33P-DXN_0-PadW17)") (class "Default")
      (node (ref "IC33") (pin "W17") (pinfunction "DXN_0_W17") (pintype "passive"))
    )
    (net (code "116") (name "unconnected-(IC33P-DXP_0-PadW18)") (class "Default")
      (node (ref "IC33") (pin "W18") (pinfunction "DXP_0_W18") (pintype "passive"))
    )
    (net (code "117") (name "unconnected-(IC33P-RDWR_B_0-PadG8)") (class "Default")
      (node (ref "IC33") (pin "G8") (pinfunction "RDWR_B_0_G8") (pintype "input+no_connect"))
    )
    (net (code "118") (name "unconnected-(IC36-RFU1-PadF1)") (class "Default")
      (node (ref "IC36") (pin "F1") (pinfunction "RFU1_F1") (pintype "input+no_connect"))
    )
    (net (code "119") (name "unconnected-(IC36-RFU2-PadH1)") (class "Default")
      (node (ref "IC36") (pin "H1") (pinfunction "RFU2_H1") (pintype "input+no_connect"))
    )
    (net (code "120") (name "unconnected-(IC36-RFU3-PadG2)") (class "Default")
      (node (ref "IC36") (pin "G2") (pinfunction "RFU3_G2") (pintype "input+no_connect"))
    )
    (net (code "121") (name "unconnected-(IC36-RFU4-PadB8)") (class "Default")
      (node (ref "IC36") (pin "B8") (pinfunction "RFU4_B8") (pintype "input+no_connect"))
    )
    (net (code "122") (name "unconnected-(IC36-RFU5-PadE8)") (class "Default")
      (node (ref "IC36") (pin "E8") (pinfunction "RFU5_E8") (pintype "input+no_connect"))
    )
  )
)
